# tda1543-iv-test.net
KiCad netlist of a schematic drawn in EAGLE
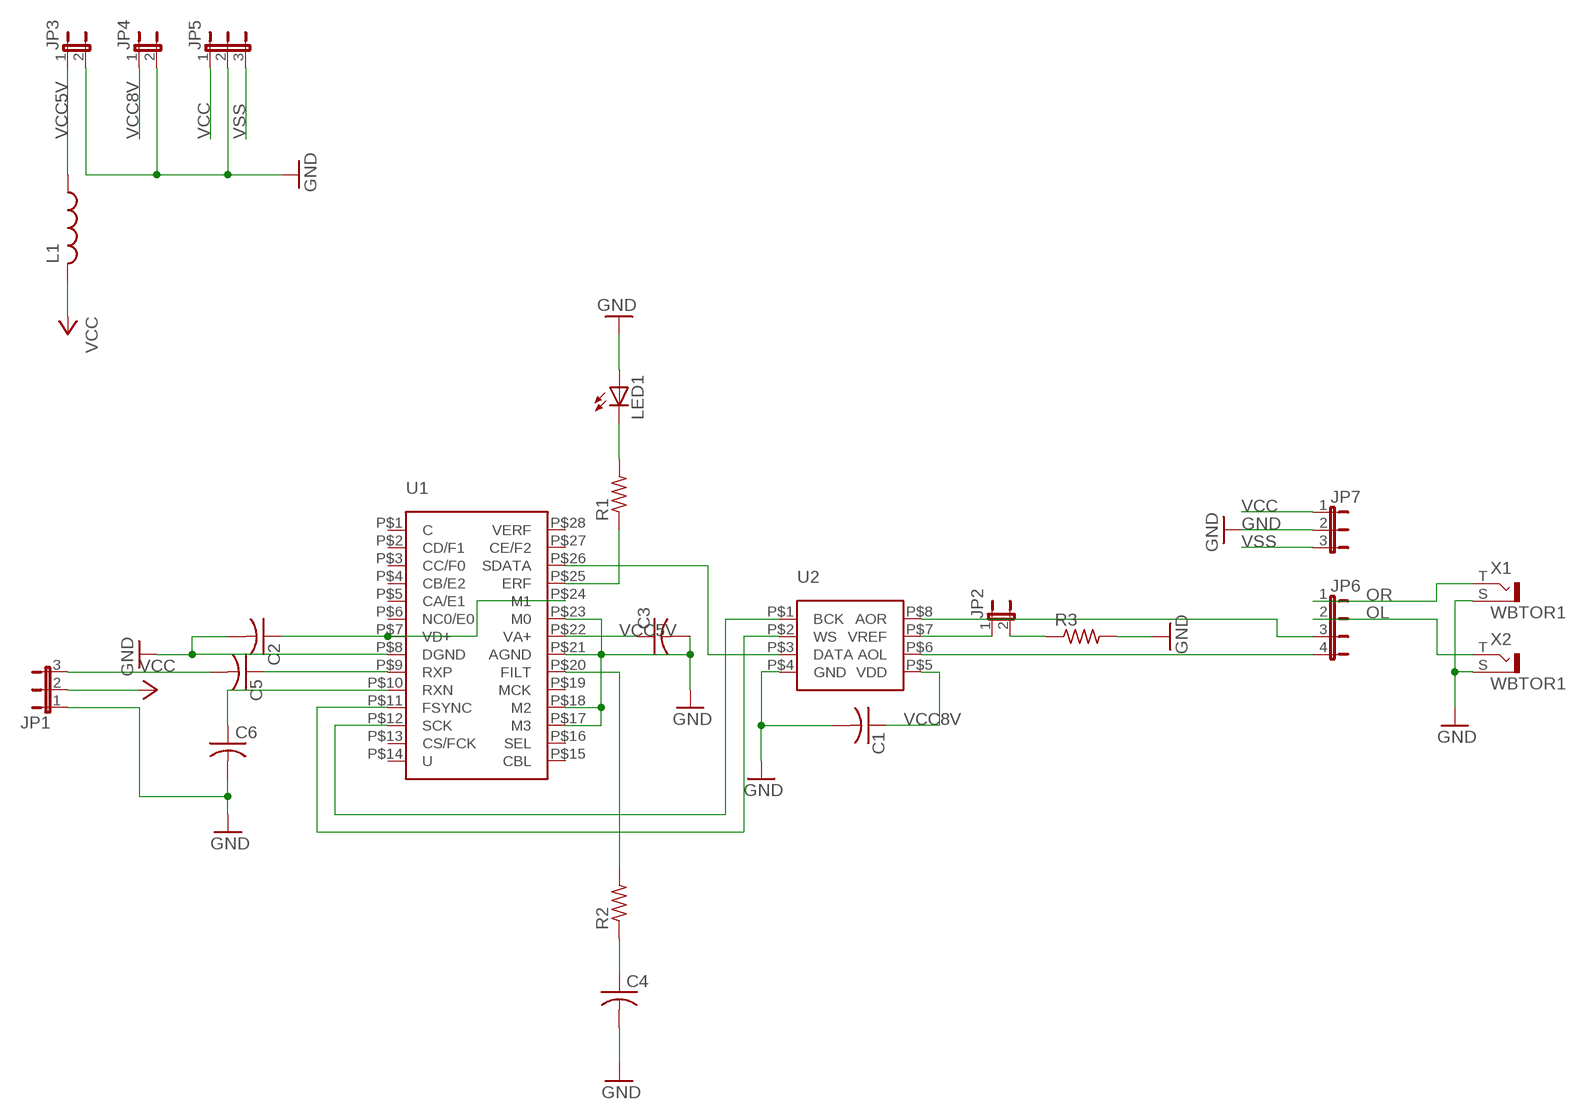
[diagram p0: schematic, sheet 1]

(export (version "E")
  (design (tool "Eeschema 10.0.6"))
  (components
    (comp (ref "C1")
      (value "C-USC0805")
      (footprint "eagle-import:C0805")
      (libsource (lib "eagle-import") (part "C-USC0805"))
    )
    (comp (ref "C2")
      (value "C-USC0805")
      (footprint "eagle-import:C0805")
      (libsource (lib "eagle-import") (part "C-USC0805"))
    )
    (comp (ref "C3")
      (value "C-USC0805")
      (footprint "eagle-import:C0805")
      (libsource (lib "eagle-import") (part "C-USC0805"))
    )
    (comp (ref "C4")
      (value "C-USC0805")
      (footprint "eagle-import:C0805")
      (libsource (lib "eagle-import") (part "C-USC0805"))
    )
    (comp (ref "C5")
      (value "C-USC0805")
      (footprint "eagle-import:C0805")
      (libsource (lib "eagle-import") (part "C-USC0805"))
    )
    (comp (ref "C6")
      (value "C-USC0805")
      (footprint "eagle-import:C0805")
      (libsource (lib "eagle-import") (part "C-USC0805"))
    )
    (comp (ref "JP1")
      (value "JP2E")
      (footprint "eagle-import:JP2")
      (libsource (lib "eagle-import") (part "JP2E"))
    )
    (comp (ref "JP2")
      (value "JP1E")
      (footprint "eagle-import:JP1")
      (libsource (lib "eagle-import") (part "JP1E"))
    )
    (comp (ref "JP3")
      (value "JP1E")
      (footprint "eagle-import:JP1")
      (libsource (lib "eagle-import") (part "JP1E"))
    )
    (comp (ref "JP4")
      (value "JP1E")
      (footprint "eagle-import:JP1")
      (libsource (lib "eagle-import") (part "JP1E"))
    )
    (comp (ref "JP5")
      (value "JP2E")
      (footprint "eagle-import:JP2")
      (libsource (lib "eagle-import") (part "JP2E"))
    )
    (comp (ref "JP6")
      (value "JP4E")
      (footprint "eagle-import:JP4")
      (libsource (lib "eagle-import") (part "JP4E"))
    )
    (comp (ref "JP7")
      (value "JP2E")
      (footprint "eagle-import:JP2")
      (libsource (lib "eagle-import") (part "JP2E"))
    )
    (comp (ref "L1")
      (value "L-USL2012C")
      (footprint "eagle-import:L2012C")
      (libsource (lib "eagle-import") (part "L-USL2012C"))
    )
    (comp (ref "LED1")
      (value "LED3MM")
      (footprint "eagle-import:LED3MM")
      (libsource (lib "eagle-import") (part "LED3MM"))
    )
    (comp (ref "R1")
      (value "R-US_R0805")
      (footprint "eagle-import:R0805")
      (libsource (lib "eagle-import") (part "R-US_R0805"))
    )
    (comp (ref "R2")
      (value "R-US_R0805")
      (footprint "eagle-import:R0805")
      (libsource (lib "eagle-import") (part "R-US_R0805"))
    )
    (comp (ref "R3")
      (value "R-US_R0805")
      (footprint "eagle-import:R0805")
      (libsource (lib "eagle-import") (part "R-US_R0805"))
    )
    (comp (ref "U1")
      (value "CS8412")
      (footprint "eagle-import:DIP14")
      (libsource (lib "eagle-import") (part "CS8412"))
    )
    (comp (ref "U2")
      (value "TDA1543")
      (footprint "eagle-import:DIP8")
      (libsource (lib "eagle-import") (part "TDA1543"))
    )
    (comp (ref "X1")
      (value "WBTOR1")
      (footprint "eagle-import:WBTOR1")
      (fields (field (name "MPN") "WBTOR 1 BLACK"))
      (libsource (lib "eagle-import") (part "WBTOR1"))
    )
    (comp (ref "X2")
      (value "WBTOR1")
      (footprint "eagle-import:WBTOR1")
      (fields (field (name "MPN") "WBTOR 1 BLACK"))
      (libsource (lib "eagle-import") (part "WBTOR1"))
    )
  )
  (nets
    (net (code "1") (name "/OL") (class "Default")
      (node (ref "JP6") (pin "2") (pinfunction "2_2") (pintype "passive"))
      (node (ref "X2") (pin "T") (pinfunction "T_T") (pintype "passive"))
    )
    (net (code "2") (name "/OR") (class "Default")
      (node (ref "JP6") (pin "1") (pinfunction "1_1") (pintype "passive"))
      (node (ref "X1") (pin "T") (pinfunction "T_T") (pintype "passive"))
    )
    (net (code "3") (name "/VCC5V") (class "Default")
      (node (ref "C3") (pin "1") (pinfunction "1_1") (pintype "passive"))
      (node (ref "JP3") (pin "1") (pinfunction "1_1") (pintype "passive"))
      (node (ref "L1") (pin "1") (pinfunction "1_1") (pintype "passive"))
      (node (ref "U1") (pin "P$22") (pinfunction "VA+_P$22") (pintype "bidirectional"))
    )
    (net (code "4") (name "/VCC8V") (class "Default")
      (node (ref "C1") (pin "1") (pinfunction "1_1") (pintype "passive"))
      (node (ref "JP4") (pin "1") (pinfunction "1_1") (pintype "passive"))
      (node (ref "U2") (pin "P$5") (pinfunction "VDD_P$5") (pintype "bidirectional"))
    )
    (net (code "5") (name "/VSS") (class "Default")
      (node (ref "JP5") (pin "3") (pinfunction "3_3") (pintype "passive"))
      (node (ref "JP7") (pin "3") (pinfunction "3_3") (pintype "passive"))
    )
    (net (code "6") (name "GND") (class "Default")
      (node (ref "C1") (pin "2") (pinfunction "2_2") (pintype "passive"))
      (node (ref "C2") (pin "2") (pinfunction "2_2") (pintype "passive"))
      (node (ref "C3") (pin "2") (pinfunction "2_2") (pintype "passive"))
      (node (ref "C4") (pin "2") (pinfunction "2_2") (pintype "passive"))
      (node (ref "C6") (pin "2") (pinfunction "2_2") (pintype "passive"))
      (node (ref "JP1") (pin "1") (pinfunction "1_1") (pintype "passive"))
      (node (ref "JP3") (pin "2") (pinfunction "2_2") (pintype "passive"))
      (node (ref "JP4") (pin "2") (pinfunction "2_2") (pintype "passive"))
      (node (ref "JP5") (pin "2") (pinfunction "2_2") (pintype "passive"))
      (node (ref "JP7") (pin "2") (pinfunction "2_2") (pintype "passive"))
      (node (ref "LED1") (pin "A") (pinfunction "A_A") (pintype "passive"))
      (node (ref "R3") (pin "2") (pinfunction "2_2") (pintype "passive"))
      (node (ref "U1") (pin "P$17") (pinfunction "M3_P$17") (pintype "bidirectional"))
      (node (ref "U1") (pin "P$18") (pinfunction "M2_P$18") (pintype "bidirectional"))
      (node (ref "U1") (pin "P$21") (pinfunction "AGND_P$21") (pintype "bidirectional"))
      (node (ref "U1") (pin "P$23") (pinfunction "M0_P$23") (pintype "bidirectional"))
      (node (ref "U1") (pin "P$8") (pinfunction "DGND_P$8") (pintype "bidirectional"))
      (node (ref "U2") (pin "P$4") (pinfunction "GND_P$4") (pintype "bidirectional"))
      (node (ref "X1") (pin "S") (pinfunction "S_S") (pintype "passive"))
      (node (ref "X2") (pin "S") (pinfunction "S_S") (pintype "passive"))
    )
    (net (code "7") (name "Net-(C4-Pad1)") (class "Default")
      (node (ref "C4") (pin "1") (pinfunction "1_1") (pintype "passive"))
      (node (ref "R2") (pin "1") (pinfunction "1_1") (pintype "passive"))
    )
    (net (code "8") (name "Net-(C5-Pad2)") (class "Default")
      (node (ref "C5") (pin "2") (pinfunction "2_2") (pintype "passive"))
      (node (ref "JP1") (pin "3") (pinfunction "3_3") (pintype "passive"))
    )
    (net (code "9") (name "Net-(JP2-Pad2)") (class "Default")
      (node (ref "JP2") (pin "2") (pinfunction "2_2") (pintype "passive"))
      (node (ref "R3") (pin "1") (pinfunction "1_1") (pintype "passive"))
    )
    (net (code "10") (name "Net-(LED1-C)") (class "Default")
      (node (ref "LED1") (pin "K") (pinfunction "C_K") (pintype "passive"))
      (node (ref "R1") (pin "2") (pinfunction "2_2") (pintype "passive"))
    )
    (net (code "11") (name "Net-(U1-ERF)") (class "Default")
      (node (ref "R1") (pin "1") (pinfunction "1_1") (pintype "passive"))
      (node (ref "U1") (pin "P$25") (pinfunction "ERF_P$25") (pintype "bidirectional"))
    )
    (net (code "12") (name "Net-(U1-FILT)") (class "Default")
      (node (ref "R2") (pin "2") (pinfunction "2_2") (pintype "passive"))
      (node (ref "U1") (pin "P$20") (pinfunction "FILT_P$20") (pintype "bidirectional"))
    )
    (net (code "13") (name "Net-(U1-FSYNC)") (class "Default")
      (node (ref "U1") (pin "P$11") (pinfunction "FSYNC_P$11") (pintype "bidirectional"))
      (node (ref "U2") (pin "P$2") (pinfunction "WS_P$2") (pintype "bidirectional"))
    )
    (net (code "14") (name "Net-(U1-M1)") (class "Default")
      (node (ref "C2") (pin "1") (pinfunction "1_1") (pintype "passive"))
      (node (ref "U1") (pin "P$24") (pinfunction "M1_P$24") (pintype "bidirectional"))
      (node (ref "U1") (pin "P$7") (pinfunction "VD+_P$7") (pintype "bidirectional"))
    )
    (net (code "15") (name "Net-(U1-RXN)") (class "Default")
      (node (ref "C6") (pin "1") (pinfunction "1_1") (pintype "passive"))
      (node (ref "U1") (pin "P$10") (pinfunction "RXN_P$10") (pintype "bidirectional"))
    )
    (net (code "16") (name "Net-(U1-RXP)") (class "Default")
      (node (ref "C5") (pin "1") (pinfunction "1_1") (pintype "passive"))
      (node (ref "U1") (pin "P$9") (pinfunction "RXP_P$9") (pintype "bidirectional"))
    )
    (net (code "17") (name "Net-(U1-SCK)") (class "Default")
      (node (ref "U1") (pin "P$12") (pinfunction "SCK_P$12") (pintype "bidirectional"))
      (node (ref "U2") (pin "P$1") (pinfunction "BCK_P$1") (pintype "bidirectional"))
    )
    (net (code "18") (name "Net-(U1-SDATA)") (class "Default")
      (node (ref "U1") (pin "P$26") (pinfunction "SDATA_P$26") (pintype "bidirectional"))
      (node (ref "U2") (pin "P$3") (pinfunction "DATA_P$3") (pintype "bidirectional"))
    )
    (net (code "19") (name "Net-(U2-AOL)") (class "Default")
      (node (ref "JP6") (pin "4") (pinfunction "4_4") (pintype "passive"))
      (node (ref "U2") (pin "P$6") (pinfunction "AOL_P$6") (pintype "bidirectional"))
    )
    (net (code "20") (name "Net-(U2-AOR)") (class "Default")
      (node (ref "JP6") (pin "3") (pinfunction "3_3") (pintype "passive"))
      (node (ref "U2") (pin "P$8") (pinfunction "AOR_P$8") (pintype "bidirectional"))
    )
    (net (code "21") (name "Net-(U2-VREF)") (class "Default")
      (node (ref "JP2") (pin "1") (pinfunction "1_1") (pintype "passive"))
      (node (ref "U2") (pin "P$7") (pinfunction "VREF_P$7") (pintype "bidirectional"))
    )
    (net (code "22") (name "VCC") (class "Default")
      (node (ref "JP1") (pin "2") (pinfunction "2_2") (pintype "passive"))
      (node (ref "JP5") (pin "1") (pinfunction "1_1") (pintype "passive"))
      (node (ref "JP7") (pin "1") (pinfunction "1_1") (pintype "passive"))
      (node (ref "L1") (pin "2") (pinfunction "2_2") (pintype "passive"))
    )
    (net (code "23") (name "unconnected-(U1-C-PadP$1)") (class "Default")
      (node (ref "U1") (pin "P$1") (pinfunction "C_P$1") (pintype "bidirectional"))
    )
    (net (code "24") (name "unconnected-(U1-CA{slash}E1-PadP$5)") (class "Default")
      (node (ref "U1") (pin "P$5") (pinfunction "CA/E1_P$5") (pintype "bidirectional"))
    )
    (net (code "25") (name "unconnected-(U1-CBL-PadP$15)") (class "Default")
      (node (ref "U1") (pin "P$15") (pinfunction "CBL_P$15") (pintype "bidirectional"))
    )
    (net (code "26") (name "unconnected-(U1-CB{slash}E2-PadP$4)") (class "Default")
      (node (ref "U1") (pin "P$4") (pinfunction "CB/E2_P$4") (pintype "bidirectional"))
    )
    (net (code "27") (name "unconnected-(U1-CC{slash}F0-PadP$3)") (class "Default")
      (node (ref "U1") (pin "P$3") (pinfunction "CC/F0_P$3") (pintype "bidirectional"))
    )
    (net (code "28") (name "unconnected-(U1-CD{slash}F1-PadP$2)") (class "Default")
      (node (ref "U1") (pin "P$2") (pinfunction "CD/F1_P$2") (pintype "bidirectional"))
    )
    (net (code "29") (name "unconnected-(U1-CE{slash}F2-PadP$27)") (class "Default")
      (node (ref "U1") (pin "P$27") (pinfunction "CE/F2_P$27") (pintype "bidirectional"))
    )
    (net (code "30") (name "unconnected-(U1-CS{slash}FCK-PadP$13)") (class "Default")
      (node (ref "U1") (pin "P$13") (pinfunction "CS/FCK_P$13") (pintype "bidirectional"))
    )
    (net (code "31") (name "unconnected-(U1-MCK-PadP$19)") (class "Default")
      (node (ref "U1") (pin "P$19") (pinfunction "MCK_P$19") (pintype "bidirectional"))
    )
    (net (code "32") (name "unconnected-(U1-NC0{slash}E0-PadP$6)") (class "Default")
      (node (ref "U1") (pin "P$6") (pinfunction "NC0/E0_P$6") (pintype "bidirectional"))
    )
    (net (code "33") (name "unconnected-(U1-SEL-PadP$16)") (class "Default")
      (node (ref "U1") (pin "P$16") (pinfunction "SEL_P$16") (pintype "bidirectional"))
    )
    (net (code "34") (name "unconnected-(U1-U-PadP$14)") (class "Default")
      (node (ref "U1") (pin "P$14") (pinfunction "U_P$14") (pintype "bidirectional"))
    )
    (net (code "35") (name "unconnected-(U1-VERF-PadP$28)") (class "Default")
      (node (ref "U1") (pin "P$28") (pinfunction "VERF_P$28") (pintype "bidirectional"))
    )
  )
)
